# auto_power.net
KiCad netlist of a schematic drawn in EAGLE
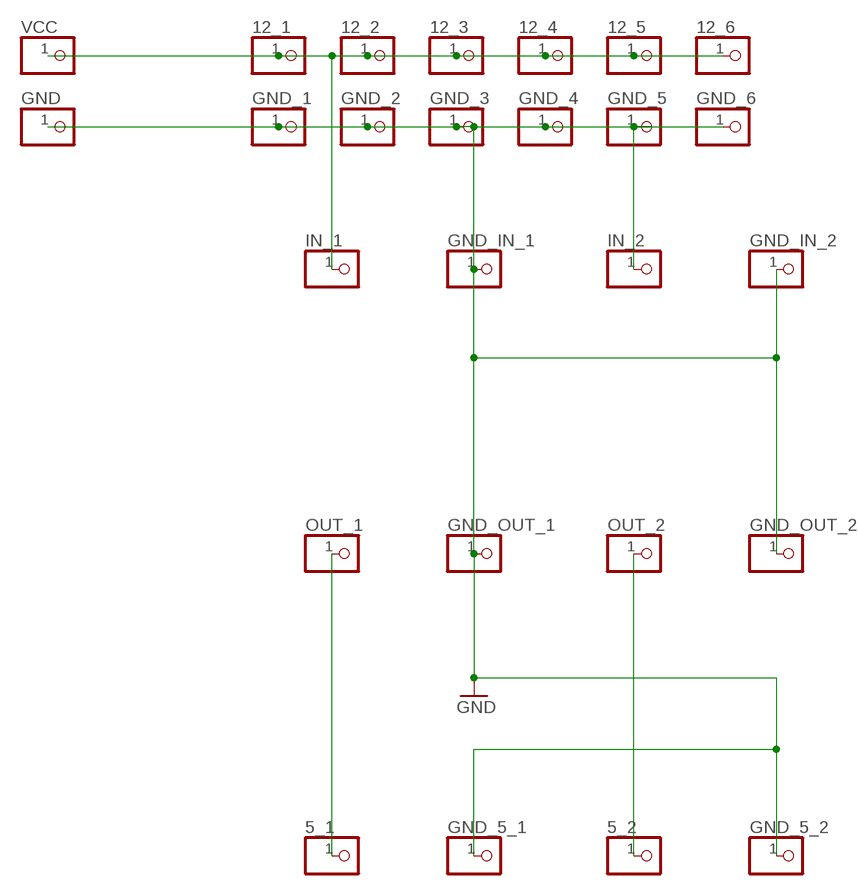
[diagram p0: schematic, sheet 1]

(export (version "E")
  (design (tool "Eeschema 10.0.6"))
  (components
    (comp (ref "5_1")
      (value "PINHD-1X1")
      (footprint "eagle-import:1X01")
      (libsource (lib "eagle-import") (part "PINHD-1X1"))
    )
    (comp (ref "5_2")
      (value "PINHD-1X1")
      (footprint "eagle-import:1X01")
      (libsource (lib "eagle-import") (part "PINHD-1X1"))
    )
    (comp (ref "12_1")
      (value "PINHD-1X1")
      (footprint "eagle-import:1X01")
      (libsource (lib "eagle-import") (part "PINHD-1X1"))
    )
    (comp (ref "12_2")
      (value "PINHD-1X1")
      (footprint "eagle-import:1X01")
      (libsource (lib "eagle-import") (part "PINHD-1X1"))
    )
    (comp (ref "12_3")
      (value "PINHD-1X1")
      (footprint "eagle-import:1X01")
      (libsource (lib "eagle-import") (part "PINHD-1X1"))
    )
    (comp (ref "12_4")
      (value "PINHD-1X1")
      (footprint "eagle-import:1X01")
      (libsource (lib "eagle-import") (part "PINHD-1X1"))
    )
    (comp (ref "12_5")
      (value "PINHD-1X1")
      (footprint "eagle-import:1X01")
      (libsource (lib "eagle-import") (part "PINHD-1X1"))
    )
    (comp (ref "12_6")
      (value "PINHD-1X1")
      (footprint "eagle-import:1X01")
      (libsource (lib "eagle-import") (part "PINHD-1X1"))
    )
    (comp (ref "GND")
      (value "PINHD-1X1")
      (footprint "eagle-import:1X01")
      (libsource (lib "eagle-import") (part "PINHD-1X1"))
    )
    (comp (ref "GND_1")
      (value "PINHD-1X1")
      (footprint "eagle-import:1X01")
      (libsource (lib "eagle-import") (part "PINHD-1X1"))
    )
    (comp (ref "GND_2")
      (value "PINHD-1X1")
      (footprint "eagle-import:1X01")
      (libsource (lib "eagle-import") (part "PINHD-1X1"))
    )
    (comp (ref "GND_3")
      (value "PINHD-1X1")
      (footprint "eagle-import:1X01")
      (libsource (lib "eagle-import") (part "PINHD-1X1"))
    )
    (comp (ref "GND_4")
      (value "PINHD-1X1")
      (footprint "eagle-import:1X01")
      (libsource (lib "eagle-import") (part "PINHD-1X1"))
    )
    (comp (ref "GND_5")
      (value "PINHD-1X1")
      (footprint "eagle-import:1X01")
      (libsource (lib "eagle-import") (part "PINHD-1X1"))
    )
    (comp (ref "GND_5_1")
      (value "PINHD-1X1")
      (footprint "eagle-import:1X01")
      (libsource (lib "eagle-import") (part "PINHD-1X1"))
    )
    (comp (ref "GND_5_2")
      (value "PINHD-1X1")
      (footprint "eagle-import:1X01")
      (libsource (lib "eagle-import") (part "PINHD-1X1"))
    )
    (comp (ref "GND_6")
      (value "PINHD-1X1")
      (footprint "eagle-import:1X01")
      (libsource (lib "eagle-import") (part "PINHD-1X1"))
    )
    (comp (ref "GND_IN_1")
      (value "PINHD-1X1")
      (footprint "eagle-import:1X01")
      (libsource (lib "eagle-import") (part "PINHD-1X1"))
    )
    (comp (ref "GND_IN_2")
      (value "PINHD-1X1")
      (footprint "eagle-import:1X01")
      (libsource (lib "eagle-import") (part "PINHD-1X1"))
    )
    (comp (ref "GND_OUT_1")
      (value "PINHD-1X1")
      (footprint "eagle-import:1X01")
      (libsource (lib "eagle-import") (part "PINHD-1X1"))
    )
    (comp (ref "GND_OUT_2")
      (value "PINHD-1X1")
      (footprint "eagle-import:1X01")
      (libsource (lib "eagle-import") (part "PINHD-1X1"))
    )
    (comp (ref "IN_1")
      (value "PINHD-1X1")
      (footprint "eagle-import:1X01")
      (libsource (lib "eagle-import") (part "PINHD-1X1"))
    )
    (comp (ref "IN_2")
      (value "PINHD-1X1")
      (footprint "eagle-import:1X01")
      (libsource (lib "eagle-import") (part "PINHD-1X1"))
    )
    (comp (ref "OUT_1")
      (value "PINHD-1X1")
      (footprint "eagle-import:1X01")
      (libsource (lib "eagle-import") (part "PINHD-1X1"))
    )
    (comp (ref "OUT_2")
      (value "PINHD-1X1")
      (footprint "eagle-import:1X01")
      (libsource (lib "eagle-import") (part "PINHD-1X1"))
    )
    (comp (ref "VCC")
      (value "PINHD-1X1")
      (footprint "eagle-import:1X01")
      (libsource (lib "eagle-import") (part "PINHD-1X1"))
    )
  )
  (nets
    (net (code "1") (name "GND") (class "Default")
      (node (ref "GND") (pin "1") (pinfunction "1_1") (pintype "passive"))
      (node (ref "GND_1") (pin "1") (pinfunction "1_1") (pintype "passive"))
      (node (ref "GND_2") (pin "1") (pinfunction "1_1") (pintype "passive"))
      (node (ref "GND_3") (pin "1") (pinfunction "1_1") (pintype "passive"))
      (node (ref "GND_4") (pin "1") (pinfunction "1_1") (pintype "passive"))
      (node (ref "GND_5") (pin "1") (pinfunction "1_1") (pintype "passive"))
      (node (ref "GND_5_1") (pin "1") (pinfunction "1_1") (pintype "passive"))
      (node (ref "GND_5_2") (pin "1") (pinfunction "1_1") (pintype "passive"))
      (node (ref "GND_6") (pin "1") (pinfunction "1_1") (pintype "passive"))
      (node (ref "GND_IN_1") (pin "1") (pinfunction "1_1") (pintype "passive"))
      (node (ref "GND_IN_2") (pin "1") (pinfunction "1_1") (pintype "passive"))
      (node (ref "GND_OUT_1") (pin "1") (pinfunction "1_1") (pintype "passive"))
      (node (ref "GND_OUT_2") (pin "1") (pinfunction "1_1") (pintype "passive"))
      (node (ref "IN_2") (pin "1") (pinfunction "1_1") (pintype "passive"))
    )
    (net (code "2") (name "Net-(5_1-Pad1)") (class "Default")
      (node (ref "5_1") (pin "1") (pinfunction "1_1") (pintype "passive"))
      (node (ref "OUT_1") (pin "1") (pinfunction "1_1") (pintype "passive"))
    )
    (net (code "3") (name "Net-(5_2-Pad1)") (class "Default")
      (node (ref "5_2") (pin "1") (pinfunction "1_1") (pintype "passive"))
      (node (ref "OUT_2") (pin "1") (pinfunction "1_1") (pintype "passive"))
    )
    (net (code "4") (name "Net-(12_1-Pad1)") (class "Default")
      (node (ref "12_1") (pin "1") (pinfunction "1_1") (pintype "passive"))
      (node (ref "12_2") (pin "1") (pinfunction "1_1") (pintype "passive"))
      (node (ref "12_3") (pin "1") (pinfunction "1_1") (pintype "passive"))
      (node (ref "12_4") (pin "1") (pinfunction "1_1") (pintype "passive"))
      (node (ref "12_5") (pin "1") (pinfunction "1_1") (pintype "passive"))
      (node (ref "12_6") (pin "1") (pinfunction "1_1") (pintype "passive"))
      (node (ref "IN_1") (pin "1") (pinfunction "1_1") (pintype "passive"))
      (node (ref "VCC") (pin "1") (pinfunction "1_1") (pintype "passive"))
    )
  )
)
